# Sheet4550.net
KiCad netlist of a schematic drawn in Altium Designer
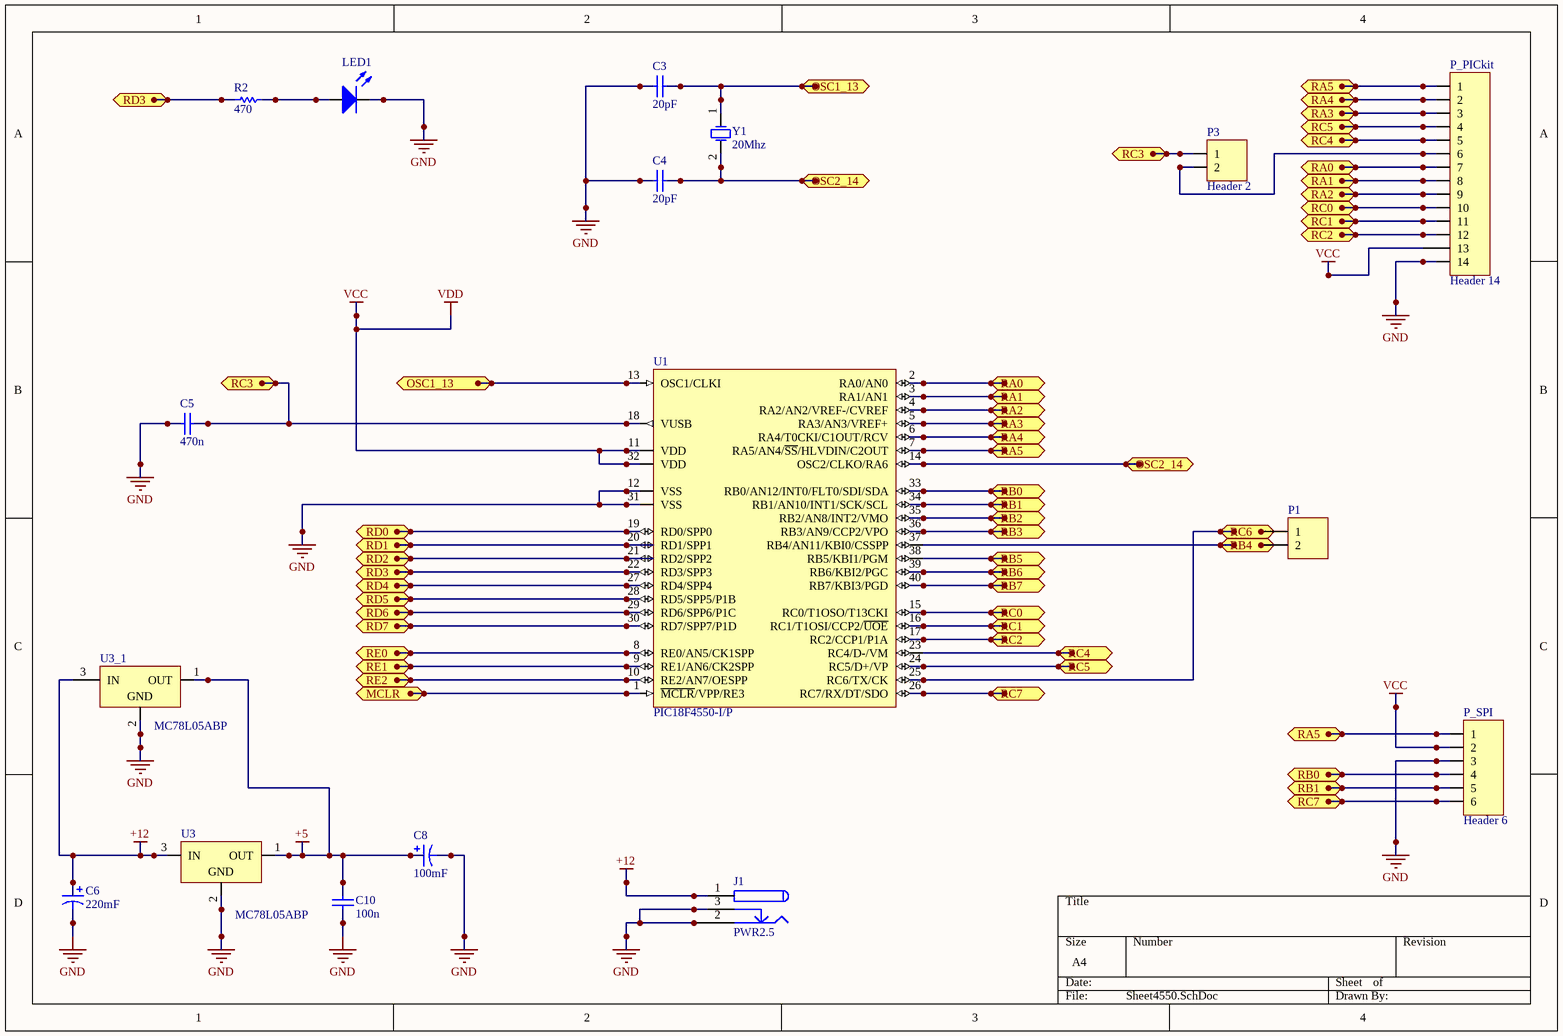
[diagram p0: Sheet4550.SchDoc]

(export (version "E")
  (design (tool "Eeschema 10.0.6"))
  (components
    (comp (ref "C3")
      (value "20pF")
      (footprint "CAPC2012L")
      (description "Capacitor (Semiconductor SIM Model)")
      (fields (field (name "PUBLISHER") "Altium Limited"))
      (libsource (lib "Miscellaneous Devices") (part "Cap Semi"))
    )
    (comp (ref "C4")
      (value "20pF")
      (footprint "CAPC2012L")
      (description "Capacitor (Semiconductor SIM Model)")
      (fields (field (name "PUBLISHER") "Altium Limited"))
      (libsource (lib "Miscellaneous Devices") (part "Cap Semi"))
    )
    (comp (ref "C5")
      (value "470n")
      (footprint "CAPC2012L")
      (description "Capacitor (Semiconductor SIM Model)")
      (fields (field (name "PUBLISHER") "Altium Limited"))
      (libsource (lib "Miscellaneous Devices") (part "Cap Semi"))
    )
    (comp (ref "C6")
      (value "220mF")
      (footprint "CAPPR5-10x12.5")
      (description "Polarized Capacitor (Radial)")
      (fields (field (name "PUBLISHER") "Altium Limited"))
      (libsource (lib "Miscellaneous Devices") (part "Cap Pol1"))
    )
    (comp (ref "C8")
      (value "100mF")
      (footprint "CAPC5764L")
      (description "Polarized Capacitor (Radial)")
      (fields (field (name "PUBLISHER") "Altium Limited"))
      (libsource (lib "Miscellaneous Devices") (part "Cap Pol1"))
    )
    (comp (ref "C10")
      (value "100n")
      (footprint "CAPC2012L")
      (description "Capacitor (Semiconductor SIM Model)")
      (fields (field (name "PUBLISHER") "Altium Limited"))
      (libsource (lib "Miscellaneous Devices") (part "Cap Semi"))
    )
    (comp (ref "J1")
      (value "PWR2.5")
      (footprint "KLD-0202")
      (description "DC Power Jack, 2.5mm, KLD Series, PCB Mount")
      (fields (field (name "PUBLISHER") "Altium Limited"))
      (libsource (lib "PCB_4550") (part "PWR2.5"))
    )
    (comp (ref "LED1")
      (value "LED2")
      (footprint "CAPC2012L")
      (description "Typical RED, GREEN, YELLOW, AMBER GaAs LED")
      (fields (field (name "PUBLISHER") "Altium Limited"))
      (libsource (lib "Miscellaneous Devices") (part "LED2"))
    )
    (comp (ref "P1")
      (value "Header 2")
      (footprint "HDR1X2")
      (description "Header, 2-Pin")
      (fields (field (name "PUBLISHER") "Altium Limited"))
      (libsource (lib "Miscellaneous Connectors") (part "Header 2"))
    )
    (comp (ref "P3")
      (value "Header 2")
      (footprint "HDR1X2")
      (description "Header, 2-Pin")
      (fields (field (name "PUBLISHER") "Altium Limited"))
      (libsource (lib "Miscellaneous Connectors") (part "Header 2"))
    )
    (comp (ref "P_PICkit")
      (value "Header 14")
      (footprint "HDR1X14")
      (description "Header, 14-Pin")
      (fields (field (name "PUBLISHER") "Altium Limited"))
      (libsource (lib "Miscellaneous Connectors") (part "Header 14"))
    )
    (comp (ref "P_SPI")
      (value "Header 6")
      (footprint "HDR1X6")
      (description "Header, 6-Pin")
      (fields (field (name "PUBLISHER") "Altium Limited"))
      (libsource (lib "Miscellaneous Connectors") (part "Header 6"))
    )
    (comp (ref "R2")
      (value "470")
      (footprint "RESC3216L")
      (description "Semiconductor Resistor")
      (fields (field (name "PUBLISHER") "Altium Limited"))
      (libsource (lib "Miscellaneous Devices") (part "Res Semi"))
    )
    (comp (ref "U1")
      (value "PIC18F4550-I/P")
      (footprint "PDIP600-P40")
      (fields (field (name "PUBLISHER") "Altium Limited"))
      (libsource (lib "Microchip Microcontroller 8-Bit PIC18") (part "PIC18F4550-I/P"))
    )
    (comp (ref "U3")
      (value "MC78L05ABP")
      (footprint "29-04")
      (description "Three-Terminal Low Current Positive Voltage Regulator")
      (fields (field (name "PUBLISHER") "Altium Limited"))
      (libsource (lib "ON Semi Power Mgt Voltage Regulator") (part "MC78L05ABP"))
    )
    (comp (ref "U3_1")
      (value "MC78L05ABP")
      (footprint "29-04")
      (description "Three-Terminal Low Current Positive Voltage Regulator")
      (fields (field (name "PUBLISHER") "Altium Limited"))
      (libsource (lib "PCB_4550") (part "MC78L05ABP"))
    )
    (comp (ref "Y1")
      (value "20Mhz")
      (footprint "SPST-2")
      (description "Crystal Oscillator")
      (fields (field (name "PUBLISHER") "Altium Limited"))
      (libsource (lib "Miscellaneous Devices") (part "XTAL"))
    )
  )
  (nets
    (net (code "1") (name "+5") (class "Default")
      (node (ref "C10") (pin "2") (pinfunction "2_2") (pintype "passive"))
      (node (ref "C8") (pin "1") (pinfunction "1_1") (pintype "passive"))
      (node (ref "U3") (pin "1") (pinfunction "OUT_1") (pintype "power_in"))
      (node (ref "U3_1") (pin "1") (pinfunction "OUT_1") (pintype "power_in"))
    )
    (net (code "2") (name "+12") (class "Default")
      (node (ref "C6") (pin "1") (pinfunction "1_1") (pintype "passive"))
      (node (ref "J1") (pin "1") (pinfunction "1_1") (pintype "power_in"))
      (node (ref "J1") (pin "1A") (pinfunction "1A_1A") (pintype "power_in"))
      (node (ref "J1") (pin "1B") (pinfunction "1B_1B") (pintype "power_in"))
      (node (ref "U3") (pin "3") (pinfunction "IN_3") (pintype "power_in"))
      (node (ref "U3_1") (pin "3") (pinfunction "IN_3") (pintype "power_in"))
    )
    (net (code "3") (name "/MCLR") (class "Default")
      (node (ref "U1") (pin "1") (pinfunction "~{MCLR}/VPP/RE3_1") (pintype "input"))
    )
    (net (code "4") (name "/OSC1_13") (class "Default")
      (node (ref "C3") (pin "2") (pinfunction "2_2") (pintype "passive"))
      (node (ref "U1") (pin "13") (pinfunction "OSC1/CLKI_13") (pintype "input"))
      (node (ref "Y1") (pin "1") (pinfunction "OSC1_1") (pintype "passive"))
    )
    (net (code "5") (name "/OSC2_14") (class "Default")
      (node (ref "C4") (pin "2") (pinfunction "2_2") (pintype "passive"))
      (node (ref "U1") (pin "14") (pinfunction "OSC2/CLKO/RA6_14") (pintype "bidirectional"))
      (node (ref "Y1") (pin "2") (pinfunction "OSC2_2") (pintype "passive"))
    )
    (net (code "6") (name "/RA0") (class "Default")
      (node (ref "P_PICkit") (pin "7") (pinfunction "7_7") (pintype "passive"))
      (node (ref "U1") (pin "2") (pinfunction "RA0/AN0_2") (pintype "bidirectional"))
    )
    (net (code "7") (name "/RA1") (class "Default")
      (node (ref "P_PICkit") (pin "8") (pinfunction "8_8") (pintype "passive"))
      (node (ref "U1") (pin "3") (pinfunction "RA1/AN1_3") (pintype "bidirectional"))
    )
    (net (code "8") (name "/RA2") (class "Default")
      (node (ref "P_PICkit") (pin "9") (pinfunction "9_9") (pintype "passive"))
      (node (ref "U1") (pin "4") (pinfunction "RA2/AN2/VREF-/CVREF_4") (pintype "bidirectional"))
    )
    (net (code "9") (name "/RA3") (class "Default")
      (node (ref "P_PICkit") (pin "3") (pinfunction "3_3") (pintype "passive"))
      (node (ref "U1") (pin "5") (pinfunction "RA3/AN3/VREF+_5") (pintype "bidirectional"))
    )
    (net (code "10") (name "/RA4") (class "Default")
      (node (ref "P_PICkit") (pin "2") (pinfunction "2_2") (pintype "passive"))
      (node (ref "U1") (pin "6") (pinfunction "RA4/T0CKI/C1OUT/RCV_6") (pintype "bidirectional"))
    )
    (net (code "11") (name "/RA5") (class "Default")
      (node (ref "P_PICkit") (pin "1") (pinfunction "1_1") (pintype "passive"))
      (node (ref "P_SPI") (pin "1") (pinfunction "1_1") (pintype "passive"))
      (node (ref "U1") (pin "7") (pinfunction "RA5/AN4/~{SS}/HLVDIN/C2OUT_7") (pintype "bidirectional"))
    )
    (net (code "12") (name "/RB0") (class "Default")
      (node (ref "P_SPI") (pin "4") (pinfunction "4_4") (pintype "passive"))
      (node (ref "U1") (pin "33") (pinfunction "RB0/AN12/INT0/FLT0/SDI/SDA_33") (pintype "bidirectional"))
    )
    (net (code "13") (name "/RB1") (class "Default")
      (node (ref "P_SPI") (pin "5") (pinfunction "5_5") (pintype "passive"))
      (node (ref "U1") (pin "34") (pinfunction "RB1/AN10/INT1/SCK/SCL_34") (pintype "bidirectional"))
    )
    (net (code "14") (name "/RB2") (class "Default")
      (node (ref "U1") (pin "35") (pinfunction "RB2/AN8/INT2/VMO_35") (pintype "bidirectional"))
    )
    (net (code "15") (name "/RB3") (class "Default")
      (node (ref "U1") (pin "36") (pinfunction "RB3/AN9/CCP2/VPO_36") (pintype "bidirectional"))
    )
    (net (code "16") (name "/RB4") (class "Default")
      (node (ref "U1") (pin "37") (pinfunction "RB4/AN11/KBI0/CSSPP_37") (pintype "bidirectional"))
    )
    (net (code "17") (name "/RB5") (class "Default")
      (node (ref "U1") (pin "38") (pinfunction "RB5/KBI1/PGM_38") (pintype "bidirectional"))
    )
    (net (code "18") (name "/RB6") (class "Default")
      (node (ref "U1") (pin "39") (pinfunction "RB6/KBI2/PGC_39") (pintype "bidirectional"))
    )
    (net (code "19") (name "/RB7") (class "Default")
      (node (ref "U1") (pin "40") (pinfunction "RB7/KBI3/PGD_40") (pintype "bidirectional"))
    )
    (net (code "20") (name "/RC0") (class "Default")
      (node (ref "P_PICkit") (pin "10") (pinfunction "10_10") (pintype "passive"))
      (node (ref "U1") (pin "15") (pinfunction "RC0/T1OSO/T13CKI_15") (pintype "bidirectional"))
    )
    (net (code "21") (name "/RC1") (class "Default")
      (node (ref "P_PICkit") (pin "11") (pinfunction "11_11") (pintype "passive"))
      (node (ref "U1") (pin "16") (pinfunction "RC1/T1OSI/CCP2/~{UOE}_16") (pintype "bidirectional"))
    )
    (net (code "22") (name "/RC2") (class "Default")
      (node (ref "P_PICkit") (pin "12") (pinfunction "12_12") (pintype "passive"))
      (node (ref "U1") (pin "17") (pinfunction "RC2/CCP1/P1A_17") (pintype "bidirectional"))
    )
    (net (code "23") (name "/RC3") (class "Default")
      (node (ref "C5") (pin "2") (pinfunction "2_2") (pintype "passive"))
      (node (ref "P3") (pin "1") (pinfunction "1_1") (pintype "passive"))
      (node (ref "U1") (pin "18") (pinfunction "VUSB_18") (pintype "output"))
    )
    (net (code "24") (name "/RC4") (class "Default")
      (node (ref "P_PICkit") (pin "5") (pinfunction "5_5") (pintype "passive"))
      (node (ref "U1") (pin "23") (pinfunction "RC4/D-/VM_23") (pintype "bidirectional"))
    )
    (net (code "25") (name "/RC5") (class "Default")
      (node (ref "P_PICkit") (pin "4") (pinfunction "4_4") (pintype "passive"))
      (node (ref "U1") (pin "24") (pinfunction "RC5/D+/VP_24") (pintype "bidirectional"))
    )
    (net (code "26") (name "/RC6") (class "Default")
      (node (ref "U1") (pin "25") (pinfunction "RC6/TX/CK_25") (pintype "bidirectional"))
    )
    (net (code "27") (name "/RC7") (class "Default")
      (node (ref "P_SPI") (pin "6") (pinfunction "6_6") (pintype "passive"))
      (node (ref "U1") (pin "26") (pinfunction "RC7/RX/DT/SDO_26") (pintype "bidirectional"))
    )
    (net (code "28") (name "/RD0") (class "Default")
      (node (ref "U1") (pin "19") (pinfunction "RD0/SPP0_19") (pintype "bidirectional"))
    )
    (net (code "29") (name "/RD1") (class "Default")
      (node (ref "U1") (pin "20") (pinfunction "RD1/SPP1_20") (pintype "bidirectional"))
    )
    (net (code "30") (name "/RD2") (class "Default")
      (node (ref "U1") (pin "21") (pinfunction "RD2/SPP2_21") (pintype "bidirectional"))
    )
    (net (code "31") (name "/RD3") (class "Default")
      (node (ref "R2") (pin "1") (pinfunction "1_1") (pintype "passive"))
      (node (ref "U1") (pin "22") (pinfunction "RD3/SPP3_22") (pintype "bidirectional"))
    )
    (net (code "32") (name "/RD4") (class "Default")
      (node (ref "U1") (pin "27") (pinfunction "RD4/SPP4_27") (pintype "bidirectional"))
    )
    (net (code "33") (name "/RD5") (class "Default")
      (node (ref "U1") (pin "28") (pinfunction "RD5/SPP5/P1B_28") (pintype "bidirectional"))
    )
    (net (code "34") (name "/RD6") (class "Default")
      (node (ref "U1") (pin "29") (pinfunction "RD6/SPP6/P1C_29") (pintype "bidirectional"))
    )
    (net (code "35") (name "/RD7") (class "Default")
      (node (ref "U1") (pin "30") (pinfunction "RD7/SPP7/P1D_30") (pintype "bidirectional"))
    )
    (net (code "36") (name "/RE0") (class "Default")
      (node (ref "U1") (pin "8") (pinfunction "RE0/AN5/CK1SPP_8") (pintype "bidirectional"))
    )
    (net (code "37") (name "/RE1") (class "Default")
      (node (ref "U1") (pin "9") (pinfunction "RE1/AN6/CK2SPP_9") (pintype "bidirectional"))
    )
    (net (code "38") (name "/RE2") (class "Default")
      (node (ref "U1") (pin "10") (pinfunction "RE2/AN7/OESPP_10") (pintype "bidirectional"))
    )
    (net (code "39") (name "GND") (class "Default")
      (node (ref "C10") (pin "1") (pinfunction "1_1") (pintype "passive"))
      (node (ref "C3") (pin "1") (pinfunction "1_1") (pintype "passive"))
      (node (ref "C4") (pin "1") (pinfunction "1_1") (pintype "passive"))
      (node (ref "C5") (pin "1") (pinfunction "1_1") (pintype "passive"))
      (node (ref "C6") (pin "2") (pinfunction "2_2") (pintype "passive"))
      (node (ref "C8") (pin "2") (pinfunction "2_2") (pintype "passive"))
      (node (ref "J1") (pin "2") (pinfunction "2_2") (pintype "power_in"))
      (node (ref "J1") (pin "2A") (pinfunction "2A_2A") (pintype "power_in"))
      (node (ref "J1") (pin "2B") (pinfunction "2B_2B") (pintype "power_in"))
      (node (ref "J1") (pin "3") (pinfunction "3_3") (pintype "power_in"))
      (node (ref "J1") (pin "3A") (pinfunction "3A_3A") (pintype "power_in"))
      (node (ref "J1") (pin "3B") (pinfunction "3B_3B") (pintype "power_in"))
      (node (ref "LED1") (pin "2") (pinfunction "K_2") (pintype "passive"))
      (node (ref "P_PICkit") (pin "14") (pinfunction "14_14") (pintype "passive"))
      (node (ref "P_SPI") (pin "3") (pinfunction "3_3") (pintype "passive"))
      (node (ref "U1") (pin "12") (pinfunction "VSS_12") (pintype "power_in"))
      (node (ref "U1") (pin "31") (pinfunction "VSS_31") (pintype "power_in"))
      (node (ref "U3") (pin "2") (pinfunction "GND_2") (pintype "power_in"))
      (node (ref "U3_1") (pin "2") (pinfunction "GND_2") (pintype "power_in"))
    )
    (net (code "40") (name "Net-(LED1-A)") (class "Default")
      (node (ref "LED1") (pin "1") (pinfunction "A_1") (pintype "passive"))
      (node (ref "R2") (pin "2") (pinfunction "2_2") (pintype "passive"))
    )
    (net (code "41") (name "Net-(P3-Pad2)") (class "Default")
      (node (ref "P3") (pin "2") (pinfunction "2_2") (pintype "passive"))
      (node (ref "P_PICkit") (pin "6") (pinfunction "6_6") (pintype "passive"))
    )
    (net (code "42") (name "VCC") (class "Default")
      (node (ref "P_PICkit") (pin "13") (pinfunction "13_13") (pintype "passive"))
      (node (ref "P_SPI") (pin "2") (pinfunction "2_2") (pintype "passive"))
      (node (ref "U1") (pin "11") (pinfunction "VDD_11") (pintype "power_in"))
      (node (ref "U1") (pin "32") (pinfunction "VDD_32") (pintype "power_in"))
    )
    (net (code "43") (name "unconnected-(P1-Pad1)") (class "Default")
      (node (ref "P1") (pin "1") (pinfunction "1_1") (pintype "passive"))
    )
    (net (code "44") (name "unconnected-(P1-Pad2)") (class "Default")
      (node (ref "P1") (pin "2") (pinfunction "2_2") (pintype "passive"))
    )
  )
)
